# F280025C_min_sys.net
KiCad netlist of a schematic drawn in Altium Designer
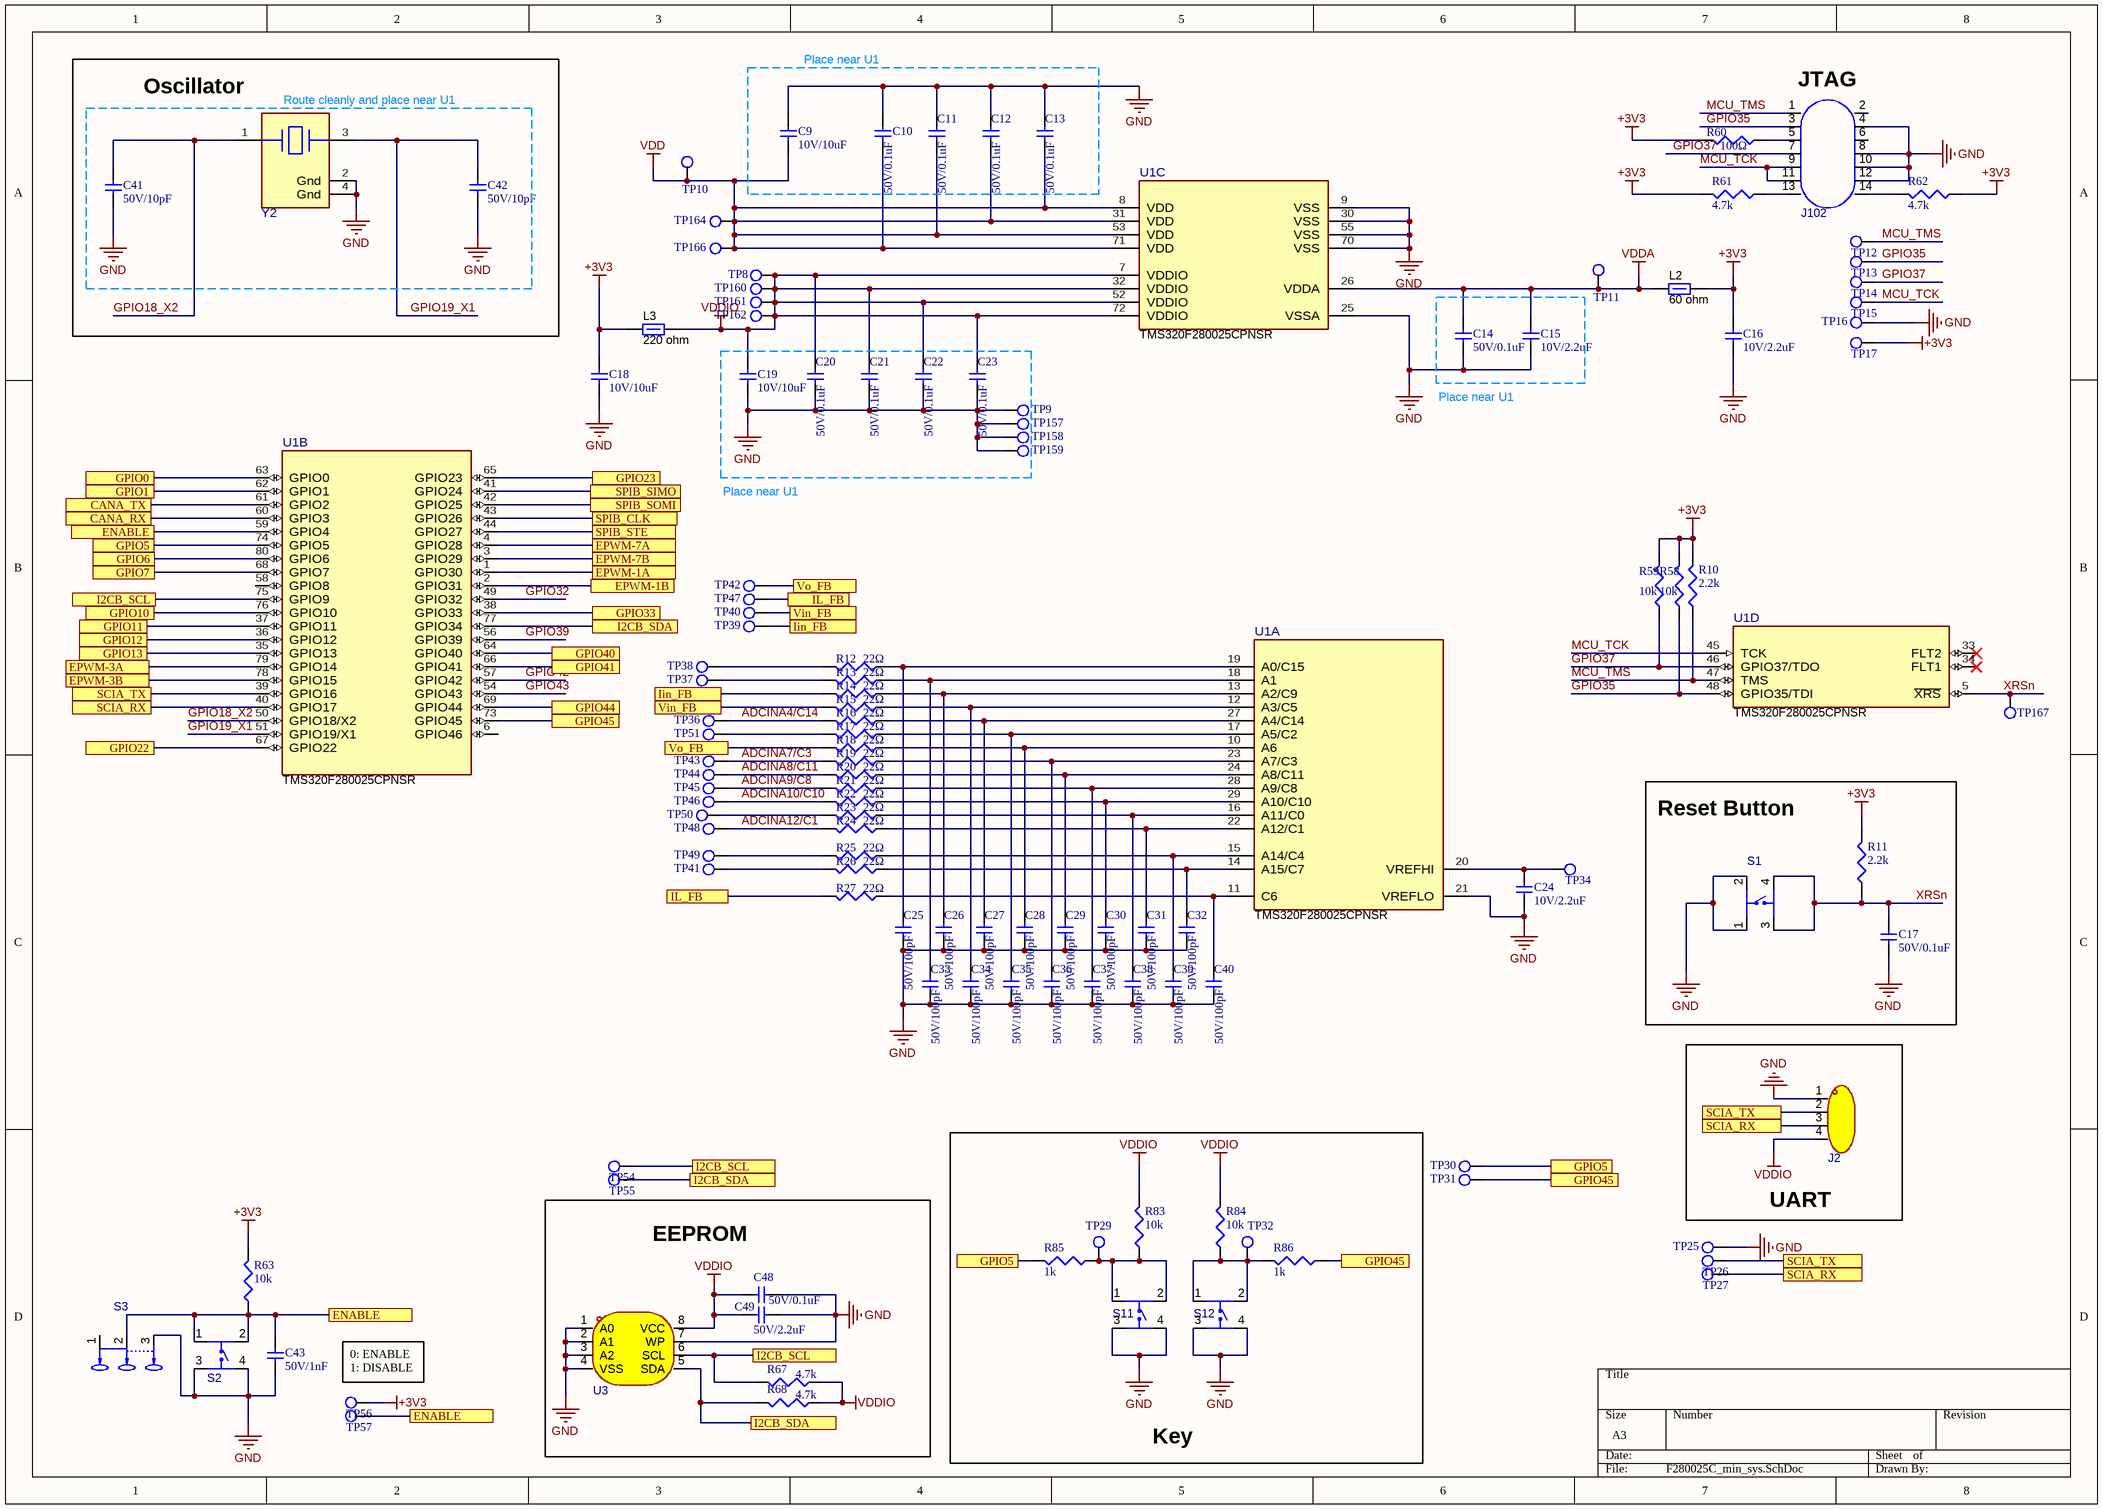
[diagram p0: F280025C_min_sys.SchDoc]

(export (version "E")
  (design (tool "Eeschema 10.0.6"))
  (components
    (comp (ref "C9")
      (value "10V/10uF")
      (footprint "C0603")
      (description "0603,10V/10uF")
      (libsource (lib "60W-PD-V2") (part "C0603-10V/10uF"))
    )
    (comp (ref "C10")
      (value "50V/0.1uF")
      (footprint "C0603")
      (description "0603,50V/104")
      (libsource (lib "60W-PD-V2") (part "C0603-50V/104"))
    )
    (comp (ref "C11")
      (value "50V/0.1uF")
      (footprint "C0603")
      (description "0603,50V/104")
      (libsource (lib "60W-PD-V2") (part "C0603-50V/104"))
    )
    (comp (ref "C12")
      (value "50V/0.1uF")
      (footprint "C0603")
      (description "0603,50V/104")
      (libsource (lib "60W-PD-V2") (part "C0603-50V/104"))
    )
    (comp (ref "C13")
      (value "50V/0.1uF")
      (footprint "C0603")
      (description "0603,50V/104")
      (libsource (lib "60W-PD-V2") (part "C0603-50V/104"))
    )
    (comp (ref "C14")
      (value "50V/0.1uF")
      (footprint "C0603")
      (description "0603,50V/104")
      (libsource (lib "60W-PD-V2") (part "C0603-50V/104"))
    )
    (comp (ref "C15")
      (value "10V/2.2uF")
      (footprint "C0603")
      (description "0603,10V/2.2uF")
      (libsource (lib "60W-PD") (part "C0603-10V/2.2uF"))
    )
    (comp (ref "C16")
      (value "10V/2.2uF")
      (footprint "C0603")
      (description "0603,10V/2.2uF")
      (libsource (lib "60W-PD") (part "C0603-10V/2.2uF"))
    )
    (comp (ref "C17")
      (value "50V/0.1uF")
      (footprint "C0603")
      (description "0603,50V/104")
      (libsource (lib "60W-PD-V2") (part "C0603-50V/104"))
    )
    (comp (ref "C18")
      (value "10V/10uF")
      (footprint "C0603")
      (description "0603,10V/10uF")
      (libsource (lib "60W-PD-V2") (part "C0603-10V/10uF"))
    )
    (comp (ref "C19")
      (value "10V/10uF")
      (footprint "C0603")
      (description "0603,10V/10uF")
      (libsource (lib "60W-PD-V2") (part "C0603-10V/10uF"))
    )
    (comp (ref "C20")
      (value "50V/0.1uF")
      (footprint "C0603")
      (description "0603,50V/104")
      (libsource (lib "60W-PD-V2") (part "C0603-50V/104"))
    )
    (comp (ref "C21")
      (value "50V/0.1uF")
      (footprint "C0603")
      (description "0603,50V/104")
      (libsource (lib "60W-PD-V2") (part "C0603-50V/104"))
    )
    (comp (ref "C22")
      (value "50V/0.1uF")
      (footprint "C0603")
      (description "0603,50V/104")
      (libsource (lib "60W-PD-V2") (part "C0603-50V/104"))
    )
    (comp (ref "C23")
      (value "50V/0.1uF")
      (footprint "C0603")
      (description "0603,50V/104")
      (libsource (lib "60W-PD-V2") (part "C0603-50V/104"))
    )
    (comp (ref "C24")
      (value "10V/2.2uF")
      (footprint "C0603")
      (description "0603,10V/2.2uF")
      (libsource (lib "60W-PD") (part "C0603-10V/2.2uF"))
    )
    (comp (ref "C25")
      (value "50V/100pF")
      (footprint "C0603")
      (description "0603,50V/100pF")
      (libsource (lib "60W-PD-V2") (part "C0603-50V/100pF"))
    )
    (comp (ref "C26")
      (value "50V/100pF")
      (footprint "C0603")
      (description "0603,50V/100pF")
      (libsource (lib "60W-PD-V2") (part "C0603-50V/100pF"))
    )
    (comp (ref "C27")
      (value "50V/100pF")
      (footprint "C0603")
      (description "0603,50V/100pF")
      (libsource (lib "60W-PD-V2") (part "C0603-50V/100pF"))
    )
    (comp (ref "C28")
      (value "50V/100pF")
      (footprint "C0603")
      (description "0603,50V/100pF")
      (libsource (lib "60W-PD-V2") (part "C0603-50V/100pF"))
    )
    (comp (ref "C29")
      (value "50V/100pF")
      (footprint "C0603")
      (description "0603,50V/100pF")
      (libsource (lib "60W-PD-V2") (part "C0603-50V/100pF"))
    )
    (comp (ref "C30")
      (value "50V/100pF")
      (footprint "C0603")
      (description "0603,50V/100pF")
      (libsource (lib "60W-PD-V2") (part "C0603-50V/100pF"))
    )
    (comp (ref "C31")
      (value "50V/100pF")
      (footprint "C0603")
      (description "0603,50V/100pF")
      (libsource (lib "60W-PD-V2") (part "C0603-50V/100pF"))
    )
    (comp (ref "C32")
      (value "50V/100pF")
      (footprint "C0603")
      (description "0603,50V/100pF")
      (libsource (lib "60W-PD-V2") (part "C0603-50V/100pF"))
    )
    (comp (ref "C33")
      (value "50V/100pF")
      (footprint "C0603")
      (description "0603,50V/100pF")
      (libsource (lib "60W-PD-V2") (part "C0603-50V/100pF"))
    )
    (comp (ref "C34")
      (value "50V/100pF")
      (footprint "C0603")
      (description "0603,50V/100pF")
      (libsource (lib "60W-PD-V2") (part "C0603-50V/100pF"))
    )
    (comp (ref "C35")
      (value "50V/100pF")
      (footprint "C0603")
      (description "0603,50V/100pF")
      (libsource (lib "60W-PD-V2") (part "C0603-50V/100pF"))
    )
    (comp (ref "C36")
      (value "50V/100pF")
      (footprint "C0603")
      (description "0603,50V/100pF")
      (libsource (lib "60W-PD-V2") (part "C0603-50V/100pF"))
    )
    (comp (ref "C37")
      (value "50V/100pF")
      (footprint "C0603")
      (description "0603,50V/100pF")
      (libsource (lib "60W-PD-V2") (part "C0603-50V/100pF"))
    )
    (comp (ref "C38")
      (value "50V/100pF")
      (footprint "C0603")
      (description "0603,50V/100pF")
      (libsource (lib "60W-PD-V2") (part "C0603-50V/100pF"))
    )
    (comp (ref "C39")
      (value "50V/100pF")
      (footprint "C0603")
      (description "0603,50V/100pF")
      (libsource (lib "60W-PD-V2") (part "C0603-50V/100pF"))
    )
    (comp (ref "C40")
      (value "50V/100pF")
      (footprint "C0603")
      (description "0603,50V/100pF")
      (libsource (lib "60W-PD-V2") (part "C0603-50V/100pF"))
    )
    (comp (ref "C41")
      (value "50V/10pF")
      (footprint "C0603")
      (description "0603,50V/10pF,C0G/NP0")
      (libsource (lib "60W-PD-V2") (part "C0603-50V/10pF"))
    )
    (comp (ref "C42")
      (value "50V/10pF")
      (footprint "C0603")
      (description "0603,50V/10pF,C0G/NP0")
      (libsource (lib "60W-PD-V2") (part "C0603-50V/10pF"))
    )
    (comp (ref "C43")
      (value "50V/1nF")
      (footprint "C0603")
      (description "0603,50V/1nF")
      (libsource (lib "60W-PD-V2") (part "C0603-50V/1nF"))
    )
    (comp (ref "C48")
      (value "50V/0.1uF")
      (footprint "C0603")
      (description "0603,50V/104")
      (libsource (lib "60W-PD-V2") (part "C0603-50V/104"))
    )
    (comp (ref "C49")
      (value "50V/2.2uF")
      (footprint "C0805")
      (description "0805,50V/2.2uF,")
      (libsource (lib "60W-PD-V2") (part "C0805-50V/2.2uF"))
    )
    (comp (ref "J2")
      (value "pz254v-11-04p")
      (footprint "HDR-TH_4P-P2.54-V-M")
      (fields (field (name "MANUFACTURER") "XFCN(兴飞)") (field (name "MANUFACTURERPART") "PZ254V-11-04P"))
      (libsource (lib "60W-PD-V2") (part "pz254v-11-04p"))
    )
    (comp (ref "J102")
      (value "2.54-2*7p简牛")
      (footprint "IDC-TH_14P-P2.54-V-R2-C7-S2.54")
      (description "连接器类型:简牛座;间距:2.54mm;结构:2x7P;安装方式:直插;行距:2.54mm;排数:2;每排PIN数:7;触头材质:黄铜;触头镀层:金;")
      (fields (field (name "MANUFACTURER") "BOOMELE(博穆精密)") (field (name "MANUFACTURERPART") "2.54-2*7P简牛"))
      (libsource (lib "60W-PD") (part "2.54-2*7p简牛"))
    )
    (comp (ref "L2")
      (value "60 ohm")
      (footprint "L0805")
      (description "磁珠,60Ω@100MHz,3A,0805,CBW201209U600T,风华")
      (fields
        (field (name "MANUFACTURER") "Wurth Elektronik")
        (field (name "PARTNUMBER") "742792063")
        (field (name "PUBLISHER") "Texas Instruments")
      )
      (libsource (lib "60W-PD") (part "磁珠-60Ω@100MHz"))
    )
    (comp (ref "L3")
      (value "220Ω/100 MHz")
      (footprint "L0805")
      (description "磁珠 220Ω @ 100 MHz, 2 A, 0805,BLM21PG221SN1D，村田")
      (fields
        (field (name "MANUFACTURER") "Wurth Elektronik")
        (field (name "PARTNUMBER") "742792022")
        (field (name "VALUEDISPLAYED") "220 ohm")
        (field (name "PUBLISHER") "Texas Instruments")
      )
      (libsource (lib "60W-PD") (part "磁珠-220Ω-100MHz-2A"))
    )
    (comp (ref "R10")
      (value "2.2k")
      (footprint "R0603")
      (description "0603,2.2k")
      (libsource (lib "60W-PD-V2") (part "R0603-2.2k"))
    )
    (comp (ref "R11")
      (value "2.2k")
      (footprint "R0603")
      (description "0603,2.2k")
      (libsource (lib "60W-PD-V2") (part "R0603-2.2k"))
    )
    (comp (ref "R12")
      (value "22Ω")
      (footprint "R0603")
      (description "0603,22Ω")
      (libsource (lib "60W-PD-V2") (part "R0603-22Ω"))
    )
    (comp (ref "R13")
      (value "22Ω")
      (footprint "R0603")
      (description "0603,22Ω")
      (libsource (lib "60W-PD-V2") (part "R0603-22Ω"))
    )
    (comp (ref "R14")
      (value "22Ω")
      (footprint "R0603")
      (description "0603,22Ω")
      (libsource (lib "60W-PD-V2") (part "R0603-22Ω"))
    )
    (comp (ref "R15")
      (value "22Ω")
      (footprint "R0603")
      (description "0603,22Ω")
      (libsource (lib "60W-PD-V2") (part "R0603-22Ω"))
    )
    (comp (ref "R16")
      (value "22Ω")
      (footprint "R0603")
      (description "0603,22Ω")
      (libsource (lib "60W-PD-V2") (part "R0603-22Ω"))
    )
    (comp (ref "R17")
      (value "22Ω")
      (footprint "R0603")
      (description "0603,22Ω")
      (libsource (lib "60W-PD-V2") (part "R0603-22Ω"))
    )
    (comp (ref "R18")
      (value "22Ω")
      (footprint "R0603")
      (description "0603,22Ω")
      (libsource (lib "60W-PD-V2") (part "R0603-22Ω"))
    )
    (comp (ref "R19")
      (value "22Ω")
      (footprint "R0603")
      (description "0603,22Ω")
      (libsource (lib "60W-PD-V2") (part "R0603-22Ω"))
    )
    (comp (ref "R20")
      (value "22Ω")
      (footprint "R0603")
      (description "0603,22Ω")
      (libsource (lib "60W-PD-V2") (part "R0603-22Ω"))
    )
    (comp (ref "R21")
      (value "22Ω")
      (footprint "R0603")
      (description "0603,22Ω")
      (libsource (lib "60W-PD-V2") (part "R0603-22Ω"))
    )
    (comp (ref "R22")
      (value "22Ω")
      (footprint "R0603")
      (description "0603,22Ω")
      (libsource (lib "60W-PD-V2") (part "R0603-22Ω"))
    )
    (comp (ref "R23")
      (value "22Ω")
      (footprint "R0603")
      (description "0603,22Ω")
      (libsource (lib "60W-PD-V2") (part "R0603-22Ω"))
    )
    (comp (ref "R24")
      (value "22Ω")
      (footprint "R0603")
      (description "0603,22Ω")
      (libsource (lib "60W-PD-V2") (part "R0603-22Ω"))
    )
    (comp (ref "R25")
      (value "22Ω")
      (footprint "R0603")
      (description "0603,22Ω")
      (libsource (lib "60W-PD-V2") (part "R0603-22Ω"))
    )
    (comp (ref "R26")
      (value "22Ω")
      (footprint "R0603")
      (description "0603,22Ω")
      (libsource (lib "60W-PD-V2") (part "R0603-22Ω"))
    )
    (comp (ref "R27")
      (value "22Ω")
      (footprint "R0603")
      (description "0603,22Ω")
      (libsource (lib "60W-PD-V2") (part "R0603-22Ω"))
    )
    (comp (ref "R58")
      (value "10k")
      (footprint "R0603")
      (description "0603,10k")
      (libsource (lib "60W-PD-V2") (part "R0603-10k"))
    )
    (comp (ref "R59")
      (value "10k")
      (footprint "R0603")
      (description "0603,10k")
      (libsource (lib "60W-PD-V2") (part "R0603-10k"))
    )
    (comp (ref "R60")
      (value "100Ω")
      (footprint "R0603")
      (description "0603,100Ω")
      (libsource (lib "60W-PD-V2") (part "R0603-100Ω"))
    )
    (comp (ref "R61")
      (value "4.7k")
      (footprint "R0603")
      (description "0603,4.7k")
      (libsource (lib "60W-PD-V2") (part "R0603-4.7k"))
    )
    (comp (ref "R62")
      (value "4.7k")
      (footprint "R0603")
      (description "0603,4.7k")
      (libsource (lib "60W-PD-V2") (part "R0603-4.7k"))
    )
    (comp (ref "R63")
      (value "10k")
      (footprint "R0603")
      (description "0603,10k")
      (libsource (lib "60W-PD-V2") (part "R0603-10k"))
    )
    (comp (ref "R67")
      (value "4.7k")
      (footprint "R0603")
      (description "0603,4.7k")
      (libsource (lib "60W-PD-V2") (part "R0603-4.7k"))
    )
    (comp (ref "R68")
      (value "4.7k")
      (footprint "R0603")
      (description "0603,4.7k")
      (libsource (lib "60W-PD-V2") (part "R0603-4.7k"))
    )
    (comp (ref "R83")
      (value "10k")
      (footprint "R0603")
      (description "0603,10k")
      (libsource (lib "60W-PD-V2") (part "R0603-10k"))
    )
    (comp (ref "R84")
      (value "10k")
      (footprint "R0603")
      (description "0603,10k")
      (libsource (lib "60W-PD-V2") (part "R0603-10k"))
    )
    (comp (ref "R85")
      (value "1k")
      (footprint "R0603")
      (description "0603,1k")
      (libsource (lib "60W-PD-V2") (part "R0603-1k"))
    )
    (comp (ref "R86")
      (value "1k")
      (footprint "R0603")
      (description "0603,1k")
      (libsource (lib "60W-PD-V2") (part "R0603-1k"))
    )
    (comp (ref "S1")
      (value "kh-6x6x5h-stm")
      (footprint "SW-SMD_4P-L6.0-W6.0-P4.50-LS9.0_H5.0")
      (description "电路结构:单刀单掷;按钮形状:圆形按钮;安装方式:立贴;开关长度:6mm;开关宽度:6mm;开关高度:5mm;带支架:不带支架;触点电流:50mA;额定电压:12V;工作寿命:8万次;")
      (fields (field (name "MANUFACTURER") "kinghelm(金航标)") (field (name "MANUFACTURERPART") "KH-6X6X5H-STM"))
      (libsource (lib "60W-PD-V2") (part "kh-6x6x5h-stm"))
    )
    (comp (ref "S2")
      (value "kh-6x6x5h-stm")
      (footprint "SW-SMD_4P-L6.0-W6.0-P4.50-LS9.0_H5.0")
      (description "电路结构:单刀单掷;按钮形状:圆形按钮;安装方式:立贴;开关长度:6mm;开关宽度:6mm;开关高度:5mm;带支架:不带支架;触点电流:50mA;额定电压:12V;工作寿命:8万次;")
      (fields (field (name "MANUFACTURER") "kinghelm(金航标)") (field (name "MANUFACTURERPART") "KH-6X6X5H-STM"))
      (libsource (lib "60W-PD-V2") (part "kh-6x6x5h-stm"))
    )
    (comp (ref "S3")
      (value "ss-12d10l5")
      (footprint "SW-TH_SS-12D10L5")
      (description "电路结构:单刀双掷;安装方式:直插;开关颜色:黑色;额定电流:3A;额定电压:125V;工作寿命:1万次;")
      (fields
        (field (name "MANUFACTURER") "XKB Connection(中国星坤)")
        (field (name "MANUFACTURERPART") "SS-12D10L5")
      )
      (libsource (lib "60W-PD") (part "ss-12d10l5"))
    )
    (comp (ref "S11")
      (value "kh-6x6x5h-stm")
      (footprint "SW-SMD_4P-L6.0-W6.0-P4.50-LS9.0_H5.0")
      (description "电路结构:单刀单掷;按钮形状:圆形按钮;安装方式:立贴;开关长度:6mm;开关宽度:6mm;开关高度:5mm;带支架:不带支架;触点电流:50mA;额定电压:12V;工作寿命:8万次;")
      (fields (field (name "MANUFACTURER") "kinghelm(金航标)") (field (name "MANUFACTURERPART") "KH-6X6X5H-STM"))
      (libsource (lib "60W-PD-V2") (part "kh-6x6x5h-stm"))
    )
    (comp (ref "S12")
      (value "kh-6x6x5h-stm")
      (footprint "SW-SMD_4P-L6.0-W6.0-P4.50-LS9.0_H5.0")
      (description "电路结构:单刀单掷;按钮形状:圆形按钮;安装方式:立贴;开关长度:6mm;开关宽度:6mm;开关高度:5mm;带支架:不带支架;触点电流:50mA;额定电压:12V;工作寿命:8万次;")
      (fields (field (name "MANUFACTURER") "kinghelm(金航标)") (field (name "MANUFACTURERPART") "KH-6X6X5H-STM"))
      (libsource (lib "60W-PD-V2") (part "kh-6x6x5h-stm"))
    )
    (comp (ref "TP8")
      (value "TEST POINT")
      (footprint "TP-1.5")
      (libsource (lib "60W-PD") (part "TEST POINT"))
    )
    (comp (ref "TP9")
      (value "TP-pad0.8")
      (footprint "PAD0.8/1.6")
      (libsource (lib "60W-PD-V2") (part "TP-pad0.8"))
    )
    (comp (ref "TP10")
      (value "TEST POINT")
      (footprint "TP-1.5")
      (libsource (lib "60W-PD") (part "TEST POINT"))
    )
    (comp (ref "TP11")
      (value "TEST POINT")
      (footprint "TP-1.5")
      (libsource (lib "60W-PD") (part "TEST POINT"))
    )
    (comp (ref "TP12")
      (value "TEST POINT")
      (footprint "TP-1.5")
      (libsource (lib "60W-PD") (part "TEST POINT"))
    )
    (comp (ref "TP13")
      (value "TEST POINT")
      (footprint "TP-1.5")
      (libsource (lib "60W-PD") (part "TEST POINT"))
    )
    (comp (ref "TP14")
      (value "TEST POINT")
      (footprint "TP-1.5")
      (libsource (lib "60W-PD") (part "TEST POINT"))
    )
    (comp (ref "TP15")
      (value "TEST POINT")
      (footprint "TP-1.5")
      (libsource (lib "60W-PD") (part "TEST POINT"))
    )
    (comp (ref "TP16")
      (value "TP-pad0.8")
      (footprint "PAD0.8/1.6")
      (libsource (lib "60W-PD-V2") (part "TP-pad0.8"))
    )
    (comp (ref "TP17")
      (value "TEST POINT")
      (footprint "TP-1.5")
      (libsource (lib "60W-PD") (part "TEST POINT"))
    )
    (comp (ref "TP25")
      (value "TP-pad0.8")
      (footprint "PAD0.8/1.6")
      (libsource (lib "60W-PD-V2") (part "TP-pad0.8"))
    )
    (comp (ref "TP26")
      (value "TEST POINT")
      (footprint "TP-1.5")
      (libsource (lib "60W-PD") (part "TEST POINT"))
    )
    (comp (ref "TP27")
      (value "TEST POINT")
      (footprint "TP-1.5")
      (libsource (lib "60W-PD") (part "TEST POINT"))
    )
    (comp (ref "TP29")
      (value "TEST POINT")
      (footprint "TP-1.5")
      (libsource (lib "60W-PD") (part "TEST POINT"))
    )
    (comp (ref "TP30")
      (value "TEST POINT")
      (footprint "TP-1.5")
      (libsource (lib "60W-PD") (part "TEST POINT"))
    )
    (comp (ref "TP31")
      (value "TEST POINT")
      (footprint "TP-1.5")
      (libsource (lib "60W-PD") (part "TEST POINT"))
    )
    (comp (ref "TP32")
      (value "TEST POINT")
      (footprint "TP-1.5")
      (libsource (lib "60W-PD") (part "TEST POINT"))
    )
    (comp (ref "TP34")
      (value "TEST POINT")
      (footprint "TP-1.5")
      (libsource (lib "60W-PD") (part "TEST POINT"))
    )
    (comp (ref "TP36")
      (value "TP-pad0.8")
      (footprint "PAD0.8/1.6")
      (libsource (lib "60W-PD-V2") (part "TP-pad0.8"))
    )
    (comp (ref "TP37")
      (value "TP-pad0.8")
      (footprint "PAD0.8/1.6")
      (libsource (lib "60W-PD-V2") (part "TP-pad0.8"))
    )
    (comp (ref "TP38")
      (value "TP-pad0.8")
      (footprint "PAD0.8/1.6")
      (libsource (lib "60W-PD-V2") (part "TP-pad0.8"))
    )
    (comp (ref "TP39")
      (value "TP-pad0.8")
      (footprint "PAD0.8/1.6")
      (libsource (lib "60W-PD-V2") (part "TP-pad0.8"))
    )
    (comp (ref "TP40")
      (value "TP-pad0.8")
      (footprint "PAD0.8/1.6")
      (libsource (lib "60W-PD-V2") (part "TP-pad0.8"))
    )
    (comp (ref "TP41")
      (value "TP-pad0.8")
      (footprint "PAD0.8/1.6")
      (libsource (lib "60W-PD-V2") (part "TP-pad0.8"))
    )
    (comp (ref "TP42")
      (value "TP-pad0.8")
      (footprint "PAD0.8/1.6")
      (libsource (lib "60W-PD-V2") (part "TP-pad0.8"))
    )
    (comp (ref "TP43")
      (value "TP-pad0.8")
      (footprint "PAD0.8/1.6")
      (libsource (lib "60W-PD-V2") (part "TP-pad0.8"))
    )
    (comp (ref "TP44")
      (value "TP-pad0.8")
      (footprint "PAD0.8/1.6")
      (libsource (lib "60W-PD-V2") (part "TP-pad0.8"))
    )
    (comp (ref "TP45")
      (value "TP-pad0.8")
      (footprint "PAD0.8/1.6")
      (libsource (lib "60W-PD-V2") (part "TP-pad0.8"))
    )
    (comp (ref "TP46")
      (value "TP-pad0.8")
      (footprint "PAD0.8/1.6")
      (libsource (lib "60W-PD-V2") (part "TP-pad0.8"))
    )
    (comp (ref "TP47")
      (value "TP-pad0.8")
      (footprint "PAD0.8/1.6")
      (libsource (lib "60W-PD-V2") (part "TP-pad0.8"))
    )
    (comp (ref "TP48")
      (value "TP-pad0.8")
      (footprint "PAD0.8/1.6")
      (libsource (lib "60W-PD-V2") (part "TP-pad0.8"))
    )
    (comp (ref "TP49")
      (value "TP-pad0.8")
      (footprint "PAD0.8/1.6")
      (libsource (lib "60W-PD-V2") (part "TP-pad0.8"))
    )
    (comp (ref "TP50")
      (value "TP-pad0.8")
      (footprint "PAD0.8/1.6")
      (libsource (lib "60W-PD-V2") (part "TP-pad0.8"))
    )
    (comp (ref "TP51")
      (value "TP-pad0.8")
      (footprint "PAD0.8/1.6")
      (libsource (lib "60W-PD-V2") (part "TP-pad0.8"))
    )
    (comp (ref "TP54")
      (value "TEST POINT")
      (footprint "TP-1.5")
      (libsource (lib "60W-PD") (part "TEST POINT"))
    )
    (comp (ref "TP55")
      (value "TEST POINT")
      (footprint "TP-1.5")
      (libsource (lib "60W-PD") (part "TEST POINT"))
    )
    (comp (ref "TP56")
      (value "TEST POINT")
      (footprint "TP-1.5")
      (libsource (lib "60W-PD") (part "TEST POINT"))
    )
    (comp (ref "TP57")
      (value "TEST POINT")
      (footprint "TP-1.5")
      (libsource (lib "60W-PD") (part "TEST POINT"))
    )
    (comp (ref "TP157")
      (value "TP-pad0.8")
      (footprint "PAD0.8/1.6")
      (libsource (lib "60W-PD-V2") (part "TP-pad0.8"))
    )
    (comp (ref "TP158")
      (value "TP-pad0.8")
      (footprint "PAD0.8/1.6")
      (libsource (lib "60W-PD-V2") (part "TP-pad0.8"))
    )
    (comp (ref "TP159")
      (value "TP-pad0.8")
      (footprint "PAD0.8/1.6")
      (libsource (lib "60W-PD-V2") (part "TP-pad0.8"))
    )
    (comp (ref "TP160")
      (value "TEST POINT")
      (footprint "TP-1.5")
      (libsource (lib "60W-PD") (part "TEST POINT"))
    )
    (comp (ref "TP161")
      (value "TEST POINT")
      (footprint "TP-1.5")
      (libsource (lib "60W-PD") (part "TEST POINT"))
    )
    (comp (ref "TP162")
      (value "TEST POINT")
      (footprint "TP-1.5")
      (libsource (lib "60W-PD") (part "TEST POINT"))
    )
    (comp (ref "TP164")
      (value "TEST POINT")
      (footprint "TP-1.5")
      (libsource (lib "60W-PD") (part "TEST POINT"))
    )
    (comp (ref "TP166")
      (value "TEST POINT")
      (footprint "TP-1.5")
      (libsource (lib "60W-PD") (part "TEST POINT"))
    )
    (comp (ref "TP167")
      (value "TEST POINT")
      (footprint "TP-1.5")
      (libsource (lib "60W-PD") (part "TEST POINT"))
    )
    (comp (ref "U1")
      (value "TMS320F280025CPNSR")
      (footprint "PN0080A-MFG")
      (description "32-bit MCU with 100 MHz, FPU, TMU, 128-KB flash, CLB 80-LQFP -40 to 125")
      (fields
        (field (name "MANUFACTURER") "Texas Instruments")
        (field (name "PARTNUMBER") "TMS320F280025CPNSR")
      )
      (libsource (lib "60W-PD") (part "SYM-TMS320F280025CPNSR"))
    )
    (comp (ref "U3")
      (value "24lc64t-i/sn")
      (footprint "SOIC-8_L4.9-W3.9-P1.27-LS6.0-BL")
      (description "接口类型:I2C;存储容量:64Kbit;时钟频率(fc):400kHz;")
      (fields
        (field (name "MANUFACTURER") "MICROCHIP(美国微芯)")
        (field (name "MANUFACTURERPART") "24LC64T-I/SN")
      )
      (libsource (lib "60W-PD-V2") (part "24lc64t-i/sn"))
    )
    (comp (ref "Y2")
      (value "20M")
      (footprint "CRYSTAL-SMD_4P-L3.2-W2.5-BL-2")
      (description "20M,X322520MSB4SI,扬兴,SMD3225-4P,常温频差:±10ppm;负载电容:20pF;频率稳定度:±20ppm;")
      (fields
        (field (name "PARTNUMBER") "ECS-200-8-30B-CKM")
        (field (name "MOUSER PART NUMBER") "520-200-8-30B-CKM")
      )
      (libsource (lib "60W-PD") (part "晶振-20M-X322520MSB4SI"))
    )
  )
  (nets
    (net (code "1") (name "+3V3") (class "Default")
      (node (ref "C16") (pin "1") (pinfunction "1_1") (pintype "passive"))
      (node (ref "C18") (pin "1") (pinfunction "1_1") (pintype "passive"))
      (node (ref "L2") (pin "2") (pinfunction "2_2") (pintype "passive"))
      (node (ref "L3") (pin "1") (pinfunction "1_1") (pintype "passive"))
      (node (ref "R10") (pin "2") (pinfunction "2_2") (pintype "passive"))
      (node (ref "R11") (pin "2") (pinfunction "2_2") (pintype "passive"))
      (node (ref "R58") (pin "2") (pinfunction "2_2") (pintype "passive"))
      (node (ref "R59") (pin "2") (pinfunction "2_2") (pintype "passive"))
      (node (ref "R60") (pin "2") (pinfunction "2_2") (pintype "passive"))
      (node (ref "R61") (pin "2") (pinfunction "2_2") (pintype "passive"))
      (node (ref "R62") (pin "1") (pinfunction "1_1") (pintype "passive"))
      (node (ref "R63") (pin "2") (pinfunction "2_2") (pintype "passive"))
      (node (ref "TP17") (pin "1") (pinfunction "1_1") (pintype "passive"))
      (node (ref "TP56") (pin "1") (pinfunction "1_1") (pintype "passive"))
    )
    (net (code "2") (name "/ADCINA4{slash}C14") (class "Default")
      (node (ref "R16") (pin "2") (pinfunction "2_2") (pintype "passive"))
      (node (ref "TP36") (pin "1") (pinfunction "1_1") (pintype "passive"))
    )
    (net (code "3") (name "/ADCINA7{slash}C3") (class "Default")
      (node (ref "R19") (pin "2") (pinfunction "2_2") (pintype "passive"))
      (node (ref "TP43") (pin "1") (pinfunction "1_1") (pintype "passive"))
    )
    (net (code "4") (name "/ADCINA8{slash}C11") (class "Default")
      (node (ref "R20") (pin "2") (pinfunction "2_2") (pintype "passive"))
      (node (ref "TP44") (pin "1") (pinfunction "1_1") (pintype "passive"))
    )
    (net (code "5") (name "/ADCINA9{slash}C8") (class "Default")
      (node (ref "R21") (pin "2") (pinfunction "2_2") (pintype "passive"))
      (node (ref "TP45") (pin "1") (pinfunction "1_1") (pintype "passive"))
    )
    (net (code "6") (name "/ADCINA10{slash}C10") (class "Default")
      (node (ref "R22") (pin "2") (pinfunction "2_2") (pintype "passive"))
      (node (ref "TP46") (pin "1") (pinfunction "1_1") (pintype "passive"))
    )
    (net (code "7") (name "/ADCINA12{slash}C1") (class "Default")
      (node (ref "R24") (pin "2") (pinfunction "2_2") (pintype "passive"))
      (node (ref "TP48") (pin "1") (pinfunction "1_1") (pintype "passive"))
    )
    (net (code "8") (name "/CANA_RX") (class "Default")
      (node (ref "U1") (pin "60") (pinfunction "GPIO3_60") (pintype "bidirectional"))
    )
    (net (code "9") (name "/CANA_TX") (class "Default")
      (node (ref "U1") (pin "61") (pinfunction "GPIO2_61") (pintype "bidirectional"))
    )
    (net (code "10") (name "/ENABLE") (class "Default")
      (node (ref "C43") (pin "1") (pinfunction "1_1") (pintype "passive"))
      (node (ref "R63") (pin "1") (pinfunction "1_1") (pintype "passive"))
      (node (ref "S2") (pin "1") (pinfunction "1_1") (pintype "passive"))
      (node (ref "S2") (pin "2") (pinfunction "2_2") (pintype "passive"))
      (node (ref "S3") (pin "2") (pinfunction "2_2") (pintype "passive"))
      (node (ref "TP57") (pin "1") (pinfunction "1_1") (pintype "passive"))
      (node (ref "U1") (pin "59") (pinfunction "GPIO4_59") (pintype "bidirectional"))
    )
    (net (code "11") (name "/EPWM-1A") (class "Default")
      (node (ref "U1") (pin "1") (pinfunction "GPIO30_1") (pintype "bidirectional"))
    )
    (net (code "12") (name "/EPWM-1B") (class "Default")
      (node (ref "U1") (pin "2") (pinfunction "GPIO31_2") (pintype "bidirectional"))
    )
    (net (code "13") (name "/EPWM-3A") (class "Default")
      (node (ref "U1") (pin "79") (pinfunction "GPIO14_79") (pintype "bidirectional"))
    )
    (net (code "14") (name "/EPWM-3B") (class "Default")
      (node (ref "U1") (pin "78") (pinfunction "GPIO15_78") (pintype "bidirectional"))
    )
    (net (code "15") (name "/EPWM-7A") (class "Default")
      (node (ref "U1") (pin "4") (pinfunction "GPIO28_4") (pintype "bidirectional"))
    )
    (net (code "16") (name "/EPWM-7B") (class "Default")
      (node (ref "U1") (pin "3") (pinfunction "GPIO29_3") (pintype "bidirectional"))
    )
    (net (code "17") (name "/GPIO0") (class "Default")
      (node (ref "U1") (pin "63") (pinfunction "GPIO0_63") (pintype "bidirectional"))
    )
    (net (code "18") (name "/GPIO1") (class "Default")
      (node (ref "U1") (pin "62") (pinfunction "GPIO1_62") (pintype "bidirectional"))
    )
    (net (code "19") (name "/GPIO5") (class "Default")
      (node (ref "R85") (pin "2") (pinfunction "2_2") (pintype "passive"))
      (node (ref "TP30") (pin "1") (pinfunction "1_1") (pintype "passive"))
      (node (ref "U1") (pin "74") (pinfunction "GPIO5_74") (pintype "bidirectional"))
    )
    (net (code "20") (name "/GPIO6") (class "Default")
      (node (ref "U1") (pin "80") (pinfunction "GPIO6_80") (pintype "bidirectional"))
    )
    (net (code "21") (name "/GPIO7") (class "Default")
      (node (ref "U1") (pin "68") (pinfunction "GPIO7_68") (pintype "bidirectional"))
    )
    (net (code "22") (name "/GPIO10") (class "Default")
      (node (ref "U1") (pin "76") (pinfunction "GPIO10_76") (pintype "bidirectional"))
    )
    (net (code "23") (name "/GPIO11") (class "Default")
      (node (ref "U1") (pin "37") (pinfunction "GPIO11_37") (pintype "bidirectional"))
    )
    (net (code "24") (name "/GPIO12") (class "Default")
      (node (ref "U1") (pin "36") (pinfunction "GPIO12_36") (pintype "bidirectional"))
    )
    (net (code "25") (name "/GPIO13") (class "Default")
      (node (ref "U1") (pin "35") (pinfunction "GPIO13_35") (pintype "bidirectional"))
    )
    (net (code "26") (name "/GPIO18_X2") (class "Default")
      (node (ref "C41") (pin "1") (pinfunction "1_1") (pintype "passive"))
      (node (ref "U1") (pin "50") (pinfunction "GPIO18/X2_50") (pintype "bidirectional"))
      (node (ref "Y2") (pin "1") (pinfunction "In/Out_1") (pintype "passive"))
    )
    (net (code "27") (name "/GPIO19_X1") (class "Default")
      (node (ref "C42") (pin "1") (pinfunction "1_1") (pintype "passive"))
      (node (ref "U1") (pin "51") (pinfunction "GPIO19/X1_51") (pintype "bidirectional"))
      (node (ref "Y2") (pin "3") (pinfunction "Out/In_3") (pintype "passive"))
    )
    (net (code "28") (name "/GPIO22") (class "Default")
      (node (ref "U1") (pin "67") (pinfunction "GPIO22_67") (pintype "bidirectional"))
    )
    (net (code "29") (name "/GPIO23") (class "Default")
      (node (ref "U1") (pin "65") (pinfunction "GPIO23_65") (pintype "bidirectional"))
    )
    (net (code "30") (name "/GPIO32") (class "Default")
      (node (ref "U1") (pin "49") (pinfunction "GPIO32_49") (pintype "bidirectional"))
    )
    (net (code "31") (name "/GPIO33") (class "Default")
      (node (ref "U1") (pin "38") (pinfunction "GPIO33_38") (pintype "bidirectional"))
    )
    (net (code "32") (name "/GPIO35") (class "Default")
      (node (ref "J102") (pin "3") (pinfunction "3_3") (pintype "passive"))
      (node (ref "R58") (pin "1") (pinfunction "1_1") (pintype "passive"))
      (node (ref "TP13") (pin "1") (pinfunction "1_1") (pintype "passive"))
      (node (ref "U1") (pin "48") (pinfunction "GPIO35/TDI_48") (pintype "bidirectional"))
    )
    (net (code "33") (name "/GPIO37") (class "Default")
      (node (ref "J102") (pin "7") (pinfunction "7_7") (pintype "passive"))
      (node (ref "R59") (pin "1") (pinfunction "1_1") (pintype "passive"))
      (node (ref "TP14") (pin "1") (pinfunction "1_1") (pintype "passive"))
      (node (ref "U1") (pin "46") (pinfunction "GPIO37/TDO_46") (pintype "bidirectional"))
    )
    (net (code "34") (name "/GPIO39") (class "Default")
      (node (ref "U1") (pin "56") (pinfunction "GPIO39_56") (pintype "bidirectional"))
    )
    (net (code "35") (name "/GPIO40") (class "Default")
      (node (ref "U1") (pin "64") (pinfunction "GPIO40_64") (pintype "bidirectional"))
    )
    (net (code "36") (name "/GPIO41") (class "Default")
      (node (ref "U1") (pin "66") (pinfunction "GPIO41_66") (pintype "bidirectional"))
    )
    (net (code "37") (name "/GPIO42") (class "Default")
      (node (ref "U1") (pin "57") (pinfunction "GPIO42_57") (pintype "bidirectional"))
    )
    (net (code "38") (name "/GPIO43") (class "Default")
      (node (ref "U1") (pin "54") (pinfunction "GPIO43_54") (pintype "bidirectional"))
    )
    (net (code "39") (name "/GPIO44") (class "Default")
      (node (ref "U1") (pin "69") (pinfunction "GPIO44_69") (pintype "bidirectional"))
    )
    (net (code "40") (name "/GPIO45") (class "Default")
      (node (ref "R86") (pin "1") (pinfunction "1_1") (pintype "passive"))
      (node (ref "TP31") (pin "1") (pinfunction "1_1") (pintype "passive"))
      (node (ref "U1") (pin "73") (pinfunction "GPIO45_73") (pintype "bidirectional"))
    )
    (net (code "41") (name "/I2CB_SCL") (class "Default")
      (node (ref "R67") (pin "2") (pinfunction "2_2") (pintype "passive"))
      (node (ref "TP54") (pin "1") (pinfunction "1_1") (pintype "passive"))
      (node (ref "U1") (pin "75") (pinfunction "GPIO9_75") (pintype "bidirectional"))
      (node (ref "U3") (pin "6") (pinfunction "SCL_6") (pintype "passive"))
    )
    (net (code "42") (name "/I2CB_SDA") (class "Default")
      (node (ref "R68") (pin "2") (pinfunction "2_2") (pintype "passive"))
      (node (ref "TP55") (pin "1") (pinfunction "1_1") (pintype "passive"))
      (node (ref "U1") (pin "77") (pinfunction "GPIO34_77") (pintype "bidirectional"))
      (node (ref "U3") (pin "5") (pinfunction "SDA_5") (pintype "passive"))
    )
    (net (code "43") (name "/IL_FB") (class "Default")
      (node (ref "R27") (pin "2") (pinfunction "2_2") (pintype "passive"))
      (node (ref "TP47") (pin "1") (pinfunction "1_1") (pintype "passive"))
    )
    (net (code "44") (name "/Iin_FB") (class "Default")
      (node (ref "R14") (pin "2") (pinfunction "2_2") (pintype "passive"))
      (node (ref "TP39") (pin "1") (pinfunction "1_1") (pintype "passive"))
    )
    (net (code "45") (name "/MCU_TCK") (class "Default")
      (node (ref "J102") (pin "11") (pinfunction "11_11") (pintype "passive"))
      (node (ref "J102") (pin "9") (pinfunction "9_9") (pintype "passive"))
      (node (ref "TP15") (pin "1") (pinfunction "1_1") (pintype "passive"))
      (node (ref "U1") (pin "45") (pinfunction "TCK_45") (pintype "input"))
    )
    (net (code "46") (name "/MCU_TMS") (class "Default")
      (node (ref "J102") (pin "1") (pinfunction "1_1") (pintype "passive"))
      (node (ref "R10") (pin "1") (pinfunction "1_1") (pintype "passive"))
      (node (ref "TP12") (pin "1") (pinfunction "1_1") (pintype "passive"))
      (node (ref "U1") (pin "47") (pinfunction "TMS_47") (pintype "bidirectional"))
    )
    (net (code "47") (name "/SCIA_RX") (class "Default")
      (node (ref "J2") (pin "3") (pinfunction "3_3") (pintype "passive"))
      (node (ref "TP27") (pin "1") (pinfunction "1_1") (pintype "passive"))
      (node (ref "U1") (pin "40") (pinfunction "GPIO17_40") (pintype "bidirectional"))
    )
    (net (code "48") (name "/SCIA_TX") (class "Default")
      (node (ref "J2") (pin "2") (pinfunction "2_2") (pintype "passive"))
      (node (ref "TP26") (pin "1") (pinfunction "1_1") (pintype "passive"))
      (node (ref "U1") (pin "39") (pinfunction "GPIO16_39") (pintype "bidirectional"))
    )
    (net (code "49") (name "/SPIB_CLK") (class "Default")
      (node (ref "U1") (pin "43") (pinfunction "GPIO26_43") (pintype "bidirectional"))
    )
    (net (code "50") (name "/SPIB_SIMO") (class "Default")
      (node (ref "U1") (pin "41") (pinfunction "GPIO24_41") (pintype "bidirectional"))
    )
    (net (code "51") (name "/SPIB_SOMI") (class "Default")
      (node (ref "U1") (pin "42") (pinfunction "GPIO25_42") (pintype "bidirectional"))
    )
    (net (code "52") (name "/SPIB_STE") (class "Default")
      (node (ref "U1") (pin "44") (pinfunction "GPIO27_44") (pintype "bidirectional"))
    )
    (net (code "53") (name "/Vin_FB") (class "Default")
      (node (ref "R15") (pin "2") (pinfunction "2_2") (pintype "passive"))
      (node (ref "TP40") (pin "1") (pinfunction "1_1") (pintype "passive"))
    )
    (net (code "54") (name "/Vo_FB") (class "Default")
      (node (ref "R18") (pin "2") (pinfunction "2_2") (pintype "passive"))
      (node (ref "TP42") (pin "1") (pinfunction "1_1") (pintype "passive"))
    )
    (net (code "55") (name "/XRSn") (class "Default")
      (node (ref "C17") (pin "1") (pinfunction "1_1") (pintype "passive"))
      (node (ref "R11") (pin "1") (pinfunction "1_1") (pintype "passive"))
      (node (ref "S1") (pin "3") (pinfunction "3_3") (pintype "passive"))
      (node (ref "S1") (pin "4") (pinfunction "4_4") (pintype "passive"))
      (node (ref "TP167") (pin "1") (pinfunction "1_1") (pintype "passive"))
      (node (ref "U1") (pin "5") (pinfunction "~{XRS}_5") (pintype "bidirectional"))
    )
    (net (code "56") (name "GND") (class "Default")
      (node (ref "C10") (pin "1") (pinfunction "1_1") (pintype "passive"))
      (node (ref "C11") (pin "1") (pinfunction "1_1") (pintype "passive"))
      (node (ref "C12") (pin "1") (pinfunction "1_1") (pintype "passive"))
      (node (ref "C13") (pin "1") (pinfunction "1_1") (pintype "passive"))
      (node (ref "C14") (pin "2") (pinfunction "2_2") (pintype "passive"))
      (node (ref "C15") (pin "2") (pinfunction "2_2") (pintype "passive"))
      (node (ref "C16") (pin "2") (pinfunction "2_2") (pintype "passive"))
      (node (ref "C17") (pin "2") (pinfunction "2_2") (pintype "passive"))
      (node (ref "C18") (pin "2") (pinfunction "2_2") (pintype "passive"))
      (node (ref "C19") (pin "2") (pinfunction "2_2") (pintype "passive"))
      (node (ref "C20") (pin "2") (pinfunction "2_2") (pintype "passive"))
      (node (ref "C21") (pin "2") (pinfunction "2_2") (pintype "passive"))
      (node (ref "C22") (pin "2") (pinfunction "2_2") (pintype "passive"))
      (node (ref "C23") (pin "2") (pinfunction "2_2") (pintype "passive"))
      (node (ref "C24") (pin "2") (pinfunction "2_2") (pintype "passive"))
      (node (ref "C25") (pin "2") (pinfunction "2_2") (pintype "passive"))
      (node (ref "C26") (pin "2") (pinfunction "2_2") (pintype "passive"))
      (node (ref "C27") (pin "2") (pinfunction "2_2") (pintype "passive"))
      (node (ref "C28") (pin "2") (pinfunction "2_2") (pintype "passive"))
      (node (ref "C29") (pin "2") (pinfunction "2_2") (pintype "passive"))
      (node (ref "C30") (pin "2") (pinfunction "2_2") (pintype "passive"))
      (node (ref "C31") (pin "2") (pinfunction "2_2") (pintype "passive"))
      (node (ref "C32") (pin "2") (pinfunction "2_2") (pintype "passive"))
      (node (ref "C33") (pin "2") (pinfunction "2_2") (pintype "passive"))
      (node (ref "C34") (pin "2") (pinfunction "2_2") (pintype "passive"))
      (node (ref "C35") (pin "2") (pinfunction "2_2") (pintype "passive"))
      (node (ref "C36") (pin "2") (pinfunction "2_2") (pintype "passive"))
      (node (ref "C37") (pin "2") (pinfunction "2_2") (pintype "passive"))
      (node (ref "C38") (pin "2") (pinfunction "2_2") (pintype "passive"))
      (node (ref "C39") (pin "2") (pinfunction "2_2") (pintype "passive"))
      (node (ref "C40") (pin "2") (pinfunction "2_2") (pintype "passive"))
      (node (ref "C41") (pin "2") (pinfunction "2_2") (pintype "passive"))
      (node (ref "C42") (pin "2") (pinfunction "2_2") (pintype "passive"))
      (node (ref "C43") (pin "2") (pinfunction "2_2") (pintype "passive"))
      (node (ref "C48") (pin "2") (pinfunction "2_2") (pintype "passive"))
      (node (ref "C49") (pin "2") (pinfunction "2_2") (pintype "passive"))
      (node (ref "C9") (pin "1") (pinfunction "1_1") (pintype "passive"))
      (node (ref "J102") (pin "10") (pinfunction "10_10") (pintype "passive"))
      (node (ref "J102") (pin "12") (pinfunction "12_12") (pintype "passive"))
      (node (ref "J102") (pin "4") (pinfunction "4_4") (pintype "passive"))
      (node (ref "J102") (pin "8") (pinfunction "8_8") (pintype "passive"))
      (node (ref "J2") (pin "1") (pinfunction "1_1") (pintype "passive"))
      (node (ref "S1") (pin "1") (pinfunction "1_1") (pintype "passive"))
      (node (ref "S1") (pin "2") (pinfunction "2_2") (pintype "passive"))
      (node (ref "S11") (pin "3") (pinfunction "3_3") (pintype "passive"))
      (node (ref "S11") (pin "4") (pinfunction "4_4") (pintype "passive"))
      (node (ref "S12") (pin "3") (pinfunction "3_3") (pintype "passive"))
      (node (ref "S12") (pin "4") (pinfunction "4_4") (pintype "passive"))
      (node (ref "S2") (pin "3") (pinfunction "3_3") (pintype "passive"))
      (node (ref "S2") (pin "4") (pinfunction "4_4") (pintype "passive"))
      (node (ref "S3") (pin "3") (pinfunction "3_3") (pintype "passive"))
      (node (ref "TP157") (pin "1") (pinfunction "1_1") (pintype "passive"))
      (node (ref "TP158") (pin "1") (pinfunction "1_1") (pintype "passive"))
      (node (ref "TP159") (pin "1") (pinfunction "1_1") (pintype "passive"))
      (node (ref "TP16") (pin "1") (pinfunction "1_1") (pintype "passive"))
      (node (ref "TP25") (pin "1") (pinfunction "1_1") (pintype "passive"))
      (node (ref "TP9") (pin "1") (pinfunction "1_1") (pintype "passive"))
      (node (ref "U1") (pin "21") (pinfunction "VREFLO_21") (pintype "passive"))
      (node (ref "U1") (pin "25") (pinfunction "VSSA_25") (pintype "power_in"))
      (node (ref "U1") (pin "30") (pinfunction "VSS_30") (pintype "power_in"))
      (node (ref "U1") (pin "55") (pinfunction "VSS_55") (pintype "power_in"))
      (node (ref "U1") (pin "70") (pinfunction "VSS_70") (pintype "power_in"))
      (node (ref "U1") (pin "9") (pinfunction "VSS_9") (pintype "power_in"))
      (node (ref "U3") (pin "1") (pinfunction "A0_1") (pintype "passive"))
      (node (ref "U3") (pin "2") (pinfunction "A1_2") (pintype "passive"))
      (node (ref "U3") (pin "3") (pinfunction "A2_3") (pintype "passive"))
      (node (ref "U3") (pin "4") (pinfunction "VSS_4") (pintype "passive"))
      (node (ref "U3") (pin "7") (pinfunction "WP_7") (pintype "passive"))
      (node (ref "Y2") (pin "2") (pinfunction "Gnd_2") (pintype "power_in"))
      (node (ref "Y2") (pin "4") (pinfunction "Gnd_4") (pintype "power_in"))
    )
    (net (code "57") (name "Net-(J102-Pad5)") (class "Default")
      (node (ref "J102") (pin "5") (pinfunction "5_5") (pintype "passive"))
      (node (ref "R60") (pin "1") (pinfunction "1_1") (pintype "passive"))
    )
    (net (code "58") (name "Net-(J102-Pad13)") (class "Default")
      (node (ref "J102") (pin "13") (pinfunction "13_13") (pintype "passive"))
      (node (ref "R61") (pin "1") (pinfunction "1_1") (pintype "passive"))
    )
    (net (code "59") (name "Net-(J102-Pad14)") (class "Default")
      (node (ref "J102") (pin "14") (pinfunction "14_14") (pintype "passive"))
      (node (ref "R62") (pin "2") (pinfunction "2_2") (pintype "passive"))
    )
    (net (code "60") (name "Net-(R12-Pad2)") (class "Default")
      (node (ref "R12") (pin "2") (pinfunction "2_2") (pintype "passive"))
      (node (ref "TP38") (pin "1") (pinfunction "1_1") (pintype "passive"))
    )
    (net (code "61") (name "Net-(R13-Pad2)") (class "Default")
      (node (ref "R13") (pin "2") (pinfunction "2_2") (pintype "passive"))
      (node (ref "TP37") (pin "1") (pinfunction "1_1") (pintype "passive"))
    )
    (net (code "62") (name "Net-(R17-Pad2)") (class "Default")
      (node (ref "R17") (pin "2") (pinfunction "2_2") (pintype "passive"))
      (node (ref "TP51") (pin "1") (pinfunction "1_1") (pintype "passive"))
    )
    (net (code "63") (name "Net-(R23-Pad2)") (class "Default")
      (node (ref "R23") (pin "2") (pinfunction "2_2") (pintype "passive"))
      (node (ref "TP50") (pin "1") (pinfunction "1_1") (pintype "passive"))
    )
    (net (code "64") (name "Net-(R25-Pad2)") (class "Default")
      (node (ref "R25") (pin "2") (pinfunction "2_2") (pintype "passive"))
      (node (ref "TP49") (pin "1") (pinfunction "1_1") (pintype "passive"))
    )
    (net (code "65") (name "Net-(R26-Pad2)") (class "Default")
      (node (ref "R26") (pin "2") (pinfunction "2_2") (pintype "passive"))
      (node (ref "TP41") (pin "1") (pinfunction "1_1") (pintype "passive"))
    )
    (net (code "66") (name "Net-(R83-Pad1)") (class "Default")
      (node (ref "R83") (pin "1") (pinfunction "1_1") (pintype "passive"))
      (node (ref "R85") (pin "1") (pinfunction "1_1") (pintype "passive"))
      (node (ref "S11") (pin "1") (pinfunction "1_1") (pintype "passive"))
      (node (ref "S11") (pin "2") (pinfunction "2_2") (pintype "passive"))
      (node (ref "TP29") (pin "1") (pinfunction "1_1") (pintype "passive"))
    )
    (net (code "67") (name "Net-(R84-Pad1)") (class "Default")
      (node (ref "R84") (pin "1") (pinfunction "1_1") (pintype "passive"))
      (node (ref "R86") (pin "2") (pinfunction "2_2") (pintype "passive"))
      (node (ref "S12") (pin "1") (pinfunction "1_1") (pintype "passive"))
      (node (ref "S12") (pin "2") (pinfunction "2_2") (pintype "passive"))
      (node (ref "TP32") (pin "1") (pinfunction "1_1") (pintype "passive"))
    )
    (net (code "68") (name "Net-(U1A-A0{slash}C15)") (class "Default")
      (node (ref "C25") (pin "1") (pinfunction "1_1") (pintype "passive"))
      (node (ref "R12") (pin "1") (pinfunction "1_1") (pintype "passive"))
      (node (ref "U1") (pin "19") (pinfunction "A0/C15_19") (pintype "passive"))
    )
    (net (code "69") (name "Net-(U1A-A1)") (class "Default")
      (node (ref "C33") (pin "1") (pinfunction "1_1") (pintype "passive"))
      (node (ref "R13") (pin "1") (pinfunction "1_1") (pintype "passive"))
      (node (ref "U1") (pin "18") (pinfunction "A1_18") (pintype "passive"))
    )
    (net (code "70") (name "Net-(U1A-A2{slash}C9)") (class "Default")
      (node (ref "C26") (pin "1") (pinfunction "1_1") (pintype "passive"))
      (node (ref "R14") (pin "1") (pinfunction "1_1") (pintype "passive"))
      (node (ref "U1") (pin "13") (pinfunction "A2/C9_13") (pintype "passive"))
    )
    (net (code "71") (name "Net-(U1A-A3{slash}C5)") (class "Default")
      (node (ref "C34") (pin "1") (pinfunction "1_1") (pintype "passive"))
      (node (ref "R15") (pin "1") (pinfunction "1_1") (pintype "passive"))
      (node (ref "U1") (pin "12") (pinfunction "A3/C5_12") (pintype "passive"))
    )
    (net (code "72") (name "Net-(U1A-A4{slash}C14)") (class "Default")
      (node (ref "C27") (pin "1") (pinfunction "1_1") (pintype "passive"))
      (node (ref "R16") (pin "1") (pinfunction "1_1") (pintype "passive"))
      (node (ref "U1") (pin "27") (pinfunction "A4/C14_27") (pintype "passive"))
    )
    (net (code "73") (name "Net-(U1A-A5{slash}C2)") (class "Default")
      (node (ref "C35") (pin "1") (pinfunction "1_1") (pintype "passive"))
      (node (ref "R17") (pin "1") (pinfunction "1_1") (pintype "passive"))
      (node (ref "U1") (pin "17") (pinfunction "A5/C2_17") (pintype "passive"))
    )
    (net (code "74") (name "Net-(U1A-A6)") (class "Default")
      (node (ref "C28") (pin "1") (pinfunction "1_1") (pintype "passive"))
      (node (ref "R18") (pin "1") (pinfunction "1_1") (pintype "passive"))
      (node (ref "U1") (pin "10") (pinfunction "A6_10") (pintype "passive"))
    )
    (net (code "75") (name "Net-(U1A-A7{slash}C3)") (class "Default")
      (node (ref "C36") (pin "1") (pinfunction "1_1") (pintype "passive"))
      (node (ref "R19") (pin "1") (pinfunction "1_1") (pintype "passive"))
      (node (ref "U1") (pin "23") (pinfunction "A7/C3_23") (pintype "passive"))
    )
    (net (code "76") (name "Net-(U1A-A8{slash}C11)") (class "Default")
      (node (ref "C29") (pin "1") (pinfunction "1_1") (pintype "passive"))
      (node (ref "R20") (pin "1") (pinfunction "1_1") (pintype "passive"))
      (node (ref "U1") (pin "24") (pinfunction "A8/C11_24") (pintype "passive"))
    )
    (net (code "77") (name "Net-(U1A-A9{slash}C8)") (class "Default")
      (node (ref "C37") (pin "1") (pinfunction "1_1") (pintype "passive"))
      (node (ref "R21") (pin "1") (pinfunction "1_1") (pintype "passive"))
      (node (ref "U1") (pin "28") (pinfunction "A9/C8_28") (pintype "passive"))
    )
    (net (code "78") (name "Net-(U1A-A10{slash}C10)") (class "Default")
      (node (ref "C30") (pin "1") (pinfunction "1_1") (pintype "passive"))
      (node (ref "R22") (pin "1") (pinfunction "1_1") (pintype "passive"))
      (node (ref "U1") (pin "29") (pinfunction "A10/C10_29") (pintype "passive"))
    )
    (net (code "79") (name "Net-(U1A-A11{slash}C0)") (class "Default")
      (node (ref "C38") (pin "1") (pinfunction "1_1") (pintype "passive"))
      (node (ref "R23") (pin "1") (pinfunction "1_1") (pintype "passive"))
      (node (ref "U1") (pin "16") (pinfunction "A11/C0_16") (pintype "passive"))
    )
    (net (code "80") (name "Net-(U1A-A12{slash}C1)") (class "Default")
      (node (ref "C31") (pin "1") (pinfunction "1_1") (pintype "passive"))
      (node (ref "R24") (pin "1") (pinfunction "1_1") (pintype "passive"))
      (node (ref "U1") (pin "22") (pinfunction "A12/C1_22") (pintype "passive"))
    )
    (net (code "81") (name "Net-(U1A-A14{slash}C4)") (class "Default")
      (node (ref "C39") (pin "1") (pinfunction "1_1") (pintype "passive"))
      (node (ref "R25") (pin "1") (pinfunction "1_1") (pintype "passive"))
      (node (ref "U1") (pin "15") (pinfunction "A14/C4_15") (pintype "passive"))
    )
    (net (code "82") (name "Net-(U1A-A15{slash}C7)") (class "Default")
      (node (ref "C32") (pin "1") (pinfunction "1_1") (pintype "passive"))
      (node (ref "R26") (pin "1") (pinfunction "1_1") (pintype "passive"))
      (node (ref "U1") (pin "14") (pinfunction "A15/C7_14") (pintype "passive"))
    )
    (net (code "83") (name "Net-(U1A-C6)") (class "Default")
      (node (ref "C40") (pin "1") (pinfunction "1_1") (pintype "passive"))
      (node (ref "R27") (pin "1") (pinfunction "1_1") (pintype "passive"))
      (node (ref "U1") (pin "11") (pinfunction "C6_11") (pintype "passive"))
    )
    (net (code "84") (name "Net-(U1A-VREFHI)") (class "Default")
      (node (ref "C24") (pin "1") (pinfunction "1_1") (pintype "passive"))
      (node (ref "TP34") (pin "1") (pinfunction "1_1") (pintype "passive"))
      (node (ref "U1") (pin "20") (pinfunction "VREFHI_20") (pintype "passive"))
    )
    (net (code "85") (name "VDD") (class "Default")
      (node (ref "C10") (pin "2") (pinfunction "2_2") (pintype "passive"))
      (node (ref "C11") (pin "2") (pinfunction "2_2") (pintype "passive"))
      (node (ref "C12") (pin "2") (pinfunction "2_2") (pintype "passive"))
      (node (ref "C13") (pin "2") (pinfunction "2_2") (pintype "passive"))
      (node (ref "C9") (pin "2") (pinfunction "2_2") (pintype "passive"))
      (node (ref "TP10") (pin "1") (pinfunction "1_1") (pintype "passive"))
      (node (ref "TP164") (pin "1") (pinfunction "1_1") (pintype "passive"))
      (node (ref "TP166") (pin "1") (pinfunction "1_1") (pintype "passive"))
      (node (ref "U1") (pin "31") (pinfunction "VDD_31") (pintype "power_in"))
      (node (ref "U1") (pin "53") (pinfunction "VDD_53") (pintype "power_in"))
      (node (ref "U1") (pin "71") (pinfunction "VDD_71") (pintype "power_in"))
      (node (ref "U1") (pin "8") (pinfunction "VDD_8") (pintype "power_in"))
    )
    (net (code "86") (name "VDDA") (class "Default")
      (node (ref "C14") (pin "1") (pinfunction "1_1") (pintype "passive"))
      (node (ref "C15") (pin "1") (pinfunction "1_1") (pintype "passive"))
      (node (ref "L2") (pin "1") (pinfunction "1_1") (pintype "passive"))
      (node (ref "TP11") (pin "1") (pinfunction "1_1") (pintype "passive"))
      (node (ref "U1") (pin "26") (pinfunction "VDDA_26") (pintype "power_in"))
    )
    (net (code "87") (name "VDDIO") (class "Default")
      (node (ref "C19") (pin "1") (pinfunction "1_1") (pintype "passive"))
      (node (ref "C20") (pin "1") (pinfunction "1_1") (pintype "passive"))
      (node (ref "C21") (pin "1") (pinfunction "1_1") (pintype "passive"))
      (node (ref "C22") (pin "1") (pinfunction "1_1") (pintype "passive"))
      (node (ref "C23") (pin "1") (pinfunction "1_1") (pintype "passive"))
      (node (ref "C48") (pin "1") (pinfunction "1_1") (pintype "passive"))
      (node (ref "C49") (pin "1") (pinfunction "1_1") (pintype "passive"))
      (node (ref "J2") (pin "4") (pinfunction "4_4") (pintype "passive"))
      (node (ref "L3") (pin "2") (pinfunction "2_2") (pintype "passive"))
      (node (ref "R67") (pin "1") (pinfunction "1_1") (pintype "passive"))
      (node (ref "R68") (pin "1") (pinfunction "1_1") (pintype "passive"))
      (node (ref "R83") (pin "2") (pinfunction "2_2") (pintype "passive"))
      (node (ref "R84") (pin "2") (pinfunction "2_2") (pintype "passive"))
      (node (ref "TP160") (pin "1") (pinfunction "1_1") (pintype "passive"))
      (node (ref "TP161") (pin "1") (pinfunction "1_1") (pintype "passive"))
      (node (ref "TP162") (pin "1") (pinfunction "1_1") (pintype "passive"))
      (node (ref "TP8") (pin "1") (pinfunction "1_1") (pintype "passive"))
      (node (ref "U1") (pin "32") (pinfunction "VDDIO_32") (pintype "power_in"))
      (node (ref "U1") (pin "52") (pinfunction "VDDIO_52") (pintype "power_in"))
      (node (ref "U1") (pin "7") (pinfunction "VDDIO_7") (pintype "power_in"))
      (node (ref "U1") (pin "72") (pinfunction "VDDIO_72") (pintype "power_in"))
      (node (ref "U3") (pin "8") (pinfunction "VCC_8") (pintype "passive"))
    )
    (net (code "88") (name "unconnected-(J102-Pad2)") (class "Default")
      (node (ref "J102") (pin "2") (pinfunction "2_2") (pintype "passive"))
    )
    (net (code "89") (name "unconnected-(J102-Pad6)") (class "Default")
      (node (ref "J102") (pin "6") (pinfunction "6_6") (pintype "passive"))
    )
    (net (code "90") (name "unconnected-(S3-Pad1)") (class "Default")
      (node (ref "S3") (pin "1") (pinfunction "1_1") (pintype "passive"))
    )
    (net (code "91") (name "unconnected-(U1B-GPIO8-Pad58)") (class "Default")
      (node (ref "U1") (pin "58") (pinfunction "GPIO8_58") (pintype "bidirectional"))
    )
    (net (code "92") (name "unconnected-(U1B-GPIO46-Pad6)") (class "Default")
      (node (ref "U1") (pin "6") (pinfunction "GPIO46_6") (pintype "bidirectional"))
    )
    (net (code "93") (name "unconnected-(U1D-FLT1-Pad34)") (class "Default")
      (node (ref "U1") (pin "34") (pinfunction "FLT1_34") (pintype "bidirectional+no_connect"))
    )
    (net (code "94") (name "unconnected-(U1D-FLT2-Pad33)") (class "Default")
      (node (ref "U1") (pin "33") (pinfunction "FLT2_33") (pintype "bidirectional+no_connect"))
    )
  )
)
